# PCB_Schematic_Sheet_1.net
KiCad netlist of a schematic drawn in Altium Designer
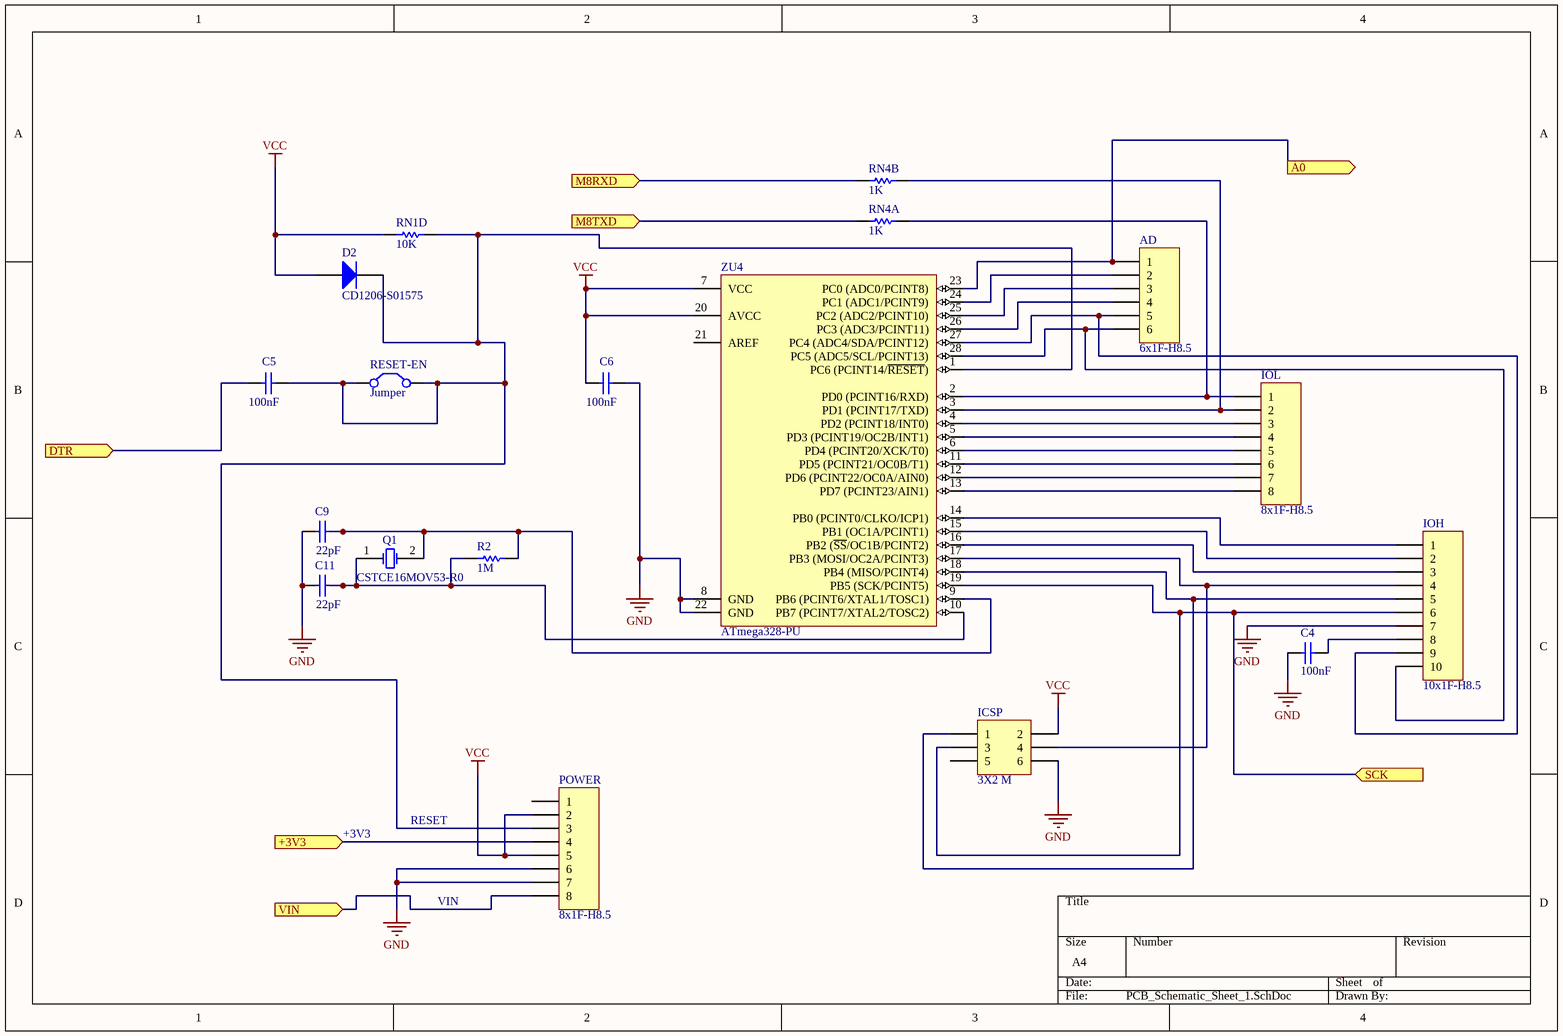
[diagram p0: PCB_Schematic_Sheet_1.SchDoc]

(export (version "E")
  (design (tool "Eeschema 10.0.6"))
  (components
    (comp (ref "AD")
      (value "6x1F-H8.5")
      (footprint "HDR1X6")
      (description "Header, 6-Pin")
      (fields (field (name "PUBLISHER") "Altium Limited"))
      (libsource (lib "Miscellaneous Connectors") (part "Header 6"))
    )
    (comp (ref "C4")
      (value "100nF")
      (footprint "CAPC0805(2012)100_M")
      (description "CAP 100nF 50V ±10% 0805 (2012 Metric) Thickness 1mm SMD")
      (fields (field (name "TOLERANCE") "Â±10%"))
      (libsource (lib "Altium Content Vault") (part "CAP"))
    )
    (comp (ref "C5")
      (value "100nF")
      (footprint "CAPC0805(2012)100_M")
      (description "CAP 100nF 50V ±10% 0805 (2012 Metric) Thickness 1mm SMD")
      (fields (field (name "TOLERANCE") "Â±10%"))
      (libsource (lib "Altium Content Vault") (part "CAP"))
    )
    (comp (ref "C6")
      (value "100nF")
      (footprint "CAPC0805(2012)100_M")
      (description "CAP 100nF 50V ±10% 0805 (2012 Metric) Thickness 1mm SMD")
      (fields (field (name "TOLERANCE") "Â±10%"))
      (libsource (lib "Altium Content Vault") (part "CAP"))
    )
    (comp (ref "C9")
      (value "22pF")
      (footprint "CAPC0805(2012)100_M")
      (description "CAP 22pF 50V ±5% 0805 (2012 Metric) Thickness 1mm SMD")
      (fields (field (name "TOLERANCE") "Â±5%"))
      (libsource (lib "Altium Content Vault") (part "CAP"))
    )
    (comp (ref "C11")
      (value "22pF")
      (footprint "CAPC0805(2012)100_M")
      (description "CAP 22pF 50V ±5% 0805 (2012 Metric) Thickness 1mm SMD")
      (fields (field (name "TOLERANCE") "Â±5%"))
      (libsource (lib "Altium Content Vault") (part "CAP"))
    )
    (comp (ref "D2")
      (value "CD1206-S01575")
      (footprint "BOUR-CD1206-S01575-2_L")
      (description "75 V Small Signal Switching Diode, 150 mA, 2.5 uA, 1026 Molded Package, RoHS, Tape and Reel")
      (fields (field (name "MANUFACTURER") "Bourns"))
      (libsource (lib "Altium Content Vault") (part "BOUR-A1K2-2"))
    )
    (comp (ref "ICSP")
      (value "3X2 M")
      (footprint "HDR2X3")
      (description "Header, 3-Pin, Dual row")
      (fields (field (name "PUBLISHER") "Altium Limited"))
      (libsource (lib "Miscellaneous Connectors") (part "Header 3X2"))
    )
    (comp (ref "IOH")
      (value "10x1F-H8.5")
      (footprint "HDR1X10")
      (description "Header, 10-Pin")
      (fields (field (name "PUBLISHER") "Altium Limited"))
      (libsource (lib "Miscellaneous Connectors") (part "Header 10"))
    )
    (comp (ref "IOL")
      (value "8x1F-H8.5")
      (footprint "HDR1X8")
      (description "Header, 8-Pin")
      (fields (field (name "PUBLISHER") "Altium Limited"))
      (libsource (lib "Miscellaneous Connectors") (part "Header 8"))
    )
    (comp (ref "POWER")
      (value "8x1F-H8.5")
      (footprint "HDR1X8")
      (description "Header, 8-Pin")
      (fields (field (name "PUBLISHER") "Altium Limited"))
      (libsource (lib "Miscellaneous Connectors") (part "Header 8"))
    )
    (comp (ref "Q1")
      (value "CSTCE16MOV53-R0")
      (footprint "R38")
      (description "Crystal Oscillator")
      (fields (field (name "PUBLISHER") "Altium Limited"))
      (libsource (lib "Miscellaneous Devices") (part "XTAL"))
    )
    (comp (ref "R2")
      (value "1M")
      (footprint "RESC0805(2012)_N")
      (description "1M 0.125W 1% 0805 (2012 Metric)  SMD")
      (fields (field (name "POWER") "0.125 W") (field (name "TOLERANCE") "1 %"))
      (libsource (lib "Altium Content Vault") (part "RES"))
    )
    (comp (ref "RESET-EN")
      (value "Jumper")
      (footprint "RAD-0.2")
      (description "Jumper Wire")
      (fields (field (name "PUBLISHER") "Altium Limited"))
      (libsource (lib "Miscellaneous Devices") (part "Jumper"))
    )
    (comp (ref "RN1D")
      (value "10K")
      (footprint "RESC0805(2012)_M")
      (description "10K 0.125W 1% 0805 (2012 Metric)  SMD")
      (fields (field (name "TOLERANCE") "1 %") (field (name "POWER") "0.125 W"))
      (libsource (lib "Altium Content Vault") (part "RES"))
    )
    (comp (ref "RN4A")
      (value "1K")
      (footprint "RESC0805(2012)_M")
      (description "1K 0.125W 1% 0805 (2012 Metric)  SMD")
      (fields (field (name "TOLERANCE") "1 %") (field (name "POWER") "0.125 W"))
      (libsource (lib "Altium Content Vault") (part "RES"))
    )
    (comp (ref "RN4B")
      (value "1K")
      (footprint "RESC0805(2012)_M")
      (description "1K 0.125W 1% 0805 (2012 Metric)  SMD")
      (fields (field (name "TOLERANCE") "1 %") (field (name "POWER") "0.125 W"))
      (libsource (lib "Altium Content Vault") (part "RES"))
    )
    (comp (ref "ZU4")
      (value "ATmega328-PU")
      (footprint "28P3")
      (libsource (lib "Altium Content Vault") (part "MC-8B-ATM48-IL28"))
    )
  )
  (nets
    (net (code "1") (name "/+3V3") (class "Default")
      (node (ref "POWER") (pin "4") (pinfunction "4_4") (pintype "passive"))
    )
    (net (code "2") (name "/A0") (class "Default")
      (node (ref "AD") (pin "1") (pinfunction "1_1") (pintype "passive"))
      (node (ref "ZU4") (pin "23") (pinfunction "PC0_(ADC0/PCINT8)_23") (pintype "bidirectional"))
    )
    (net (code "3") (name "/DTR") (class "Default")
      (node (ref "C5") (pin "1") (pinfunction "1_1") (pintype "passive"))
    )
    (net (code "4") (name "/M8RXD") (class "Default")
      (node (ref "RN4B") (pin "1") (pinfunction "1_1") (pintype "passive"))
    )
    (net (code "5") (name "/M8TXD") (class "Default")
      (node (ref "RN4A") (pin "1") (pinfunction "1_1") (pintype "passive"))
    )
    (net (code "6") (name "/SCK") (class "Default")
      (node (ref "ICSP") (pin "3") (pinfunction "3_3") (pintype "passive"))
      (node (ref "IOH") (pin "6") (pinfunction "6_6") (pintype "passive"))
      (node (ref "ZU4") (pin "19") (pinfunction "PB5_(SCK/PCINT5)_19") (pintype "bidirectional"))
    )
    (net (code "7") (name "/VIN") (class "Default")
      (node (ref "POWER") (pin "8") (pinfunction "8_8") (pintype "passive"))
    )
    (net (code "8") (name "GND") (class "Default")
      (node (ref "C11") (pin "1") (pinfunction "1_1") (pintype "passive"))
      (node (ref "C4") (pin "1") (pinfunction "1_1") (pintype "passive"))
      (node (ref "C6") (pin "2") (pinfunction "2_2") (pintype "passive"))
      (node (ref "C9") (pin "1") (pinfunction "1_1") (pintype "passive"))
      (node (ref "ICSP") (pin "6") (pinfunction "6_6") (pintype "passive"))
      (node (ref "IOH") (pin "7") (pinfunction "7_7") (pintype "passive"))
      (node (ref "POWER") (pin "6") (pinfunction "6_6") (pintype "passive"))
      (node (ref "POWER") (pin "7") (pinfunction "7_7") (pintype "passive"))
      (node (ref "ZU4") (pin "22") (pinfunction "GND_22") (pintype "power_in"))
      (node (ref "ZU4") (pin "8") (pinfunction "GND_8") (pintype "power_in"))
    )
    (net (code "9") (name "Net-(C4-Pad2)") (class "Default")
      (node (ref "C4") (pin "2") (pinfunction "2_2") (pintype "passive"))
      (node (ref "IOH") (pin "8") (pinfunction "8_8") (pintype "passive"))
    )
    (net (code "10") (name "Net-(D2-K)") (class "Default")
      (node (ref "C5") (pin "2") (pinfunction "2_2") (pintype "passive"))
      (node (ref "D2") (pin "2") (pinfunction "K_2") (pintype "passive"))
      (node (ref "POWER") (pin "3") (pinfunction "3_3") (pintype "passive"))
      (node (ref "RESET-EN") (pin "1") (pinfunction "C1_1") (pintype "passive"))
      (node (ref "RESET-EN") (pin "2") (pinfunction "C2_2") (pintype "passive"))
      (node (ref "RN1D") (pin "2") (pinfunction "2_2") (pintype "passive"))
      (node (ref "ZU4") (pin "1") (pinfunction "PC6_(PCINT14/~{RESET})_1") (pintype "bidirectional"))
    )
    (net (code "11") (name "Net-(Q1-OSC1)") (class "Default")
      (node (ref "C11") (pin "2") (pinfunction "2_2") (pintype "passive"))
      (node (ref "Q1") (pin "1") (pinfunction "OSC1_1") (pintype "passive"))
      (node (ref "R2") (pin "1") (pinfunction "1_1") (pintype "passive"))
      (node (ref "ZU4") (pin "10") (pinfunction "PB7_(PCINT7/XTAL2/TOSC2)_10") (pintype "bidirectional"))
    )
    (net (code "12") (name "Net-(Q1-OSC2)") (class "Default")
      (node (ref "C9") (pin "2") (pinfunction "2_2") (pintype "passive"))
      (node (ref "Q1") (pin "2") (pinfunction "OSC2_2") (pintype "passive"))
      (node (ref "R2") (pin "2") (pinfunction "2_2") (pintype "passive"))
      (node (ref "ZU4") (pin "9") (pinfunction "PB6_(PCINT6/XTAL1/TOSC1)_9") (pintype "bidirectional"))
    )
    (net (code "13") (name "Net-(ZU4-PB0_(PCINT0{slash}CLKO{slash}ICP1))") (class "Default")
      (node (ref "IOH") (pin "1") (pinfunction "1_1") (pintype "passive"))
      (node (ref "ZU4") (pin "14") (pinfunction "PB0_(PCINT0/CLKO/ICP1)_14") (pintype "bidirectional"))
    )
    (net (code "14") (name "Net-(ZU4-PB1_(OC1A{slash}PCINT1))") (class "Default")
      (node (ref "IOH") (pin "2") (pinfunction "2_2") (pintype "passive"))
      (node (ref "ZU4") (pin "15") (pinfunction "PB1_(OC1A/PCINT1)_15") (pintype "bidirectional"))
    )
    (net (code "15") (name "Net-(ZU4-PB2_(~{SS}{slash}OC1B{slash}PCINT2))") (class "Default")
      (node (ref "IOH") (pin "3") (pinfunction "3_3") (pintype "passive"))
      (node (ref "ZU4") (pin "16") (pinfunction "PB2_(~{SS}/OC1B/PCINT2)_16") (pintype "bidirectional"))
    )
    (net (code "16") (name "Net-(ZU4-PB3_(MOSI{slash}OC2A{slash}PCINT3))") (class "Default")
      (node (ref "ICSP") (pin "4") (pinfunction "4_4") (pintype "passive"))
      (node (ref "IOH") (pin "4") (pinfunction "4_4") (pintype "passive"))
      (node (ref "ZU4") (pin "17") (pinfunction "PB3_(MOSI/OC2A/PCINT3)_17") (pintype "bidirectional"))
    )
    (net (code "17") (name "Net-(ZU4-PB4_(MISO{slash}PCINT4))") (class "Default")
      (node (ref "ICSP") (pin "1") (pinfunction "1_1") (pintype "passive"))
      (node (ref "IOH") (pin "5") (pinfunction "5_5") (pintype "passive"))
      (node (ref "ZU4") (pin "18") (pinfunction "PB4_(MISO/PCINT4)_18") (pintype "bidirectional"))
    )
    (net (code "18") (name "Net-(ZU4-PC1_(ADC1{slash}PCINT9))") (class "Default")
      (node (ref "AD") (pin "2") (pinfunction "2_2") (pintype "passive"))
      (node (ref "ZU4") (pin "24") (pinfunction "PC1_(ADC1/PCINT9)_24") (pintype "bidirectional"))
    )
    (net (code "19") (name "Net-(ZU4-PC2_(ADC2{slash}PCINT10))") (class "Default")
      (node (ref "AD") (pin "3") (pinfunction "3_3") (pintype "passive"))
      (node (ref "ZU4") (pin "25") (pinfunction "PC2_(ADC2/PCINT10)_25") (pintype "bidirectional"))
    )
    (net (code "20") (name "Net-(ZU4-PC3_(ADC3{slash}PCINT11))") (class "Default")
      (node (ref "AD") (pin "4") (pinfunction "4_4") (pintype "passive"))
      (node (ref "ZU4") (pin "26") (pinfunction "PC3_(ADC3/PCINT11)_26") (pintype "bidirectional"))
    )
    (net (code "21") (name "Net-(ZU4-PC4_(ADC4{slash}SDA{slash}PCINT12))") (class "Default")
      (node (ref "AD") (pin "5") (pinfunction "5_5") (pintype "passive"))
      (node (ref "IOH") (pin "9") (pinfunction "9_9") (pintype "passive"))
      (node (ref "ZU4") (pin "27") (pinfunction "PC4_(ADC4/SDA/PCINT12)_27") (pintype "bidirectional"))
    )
    (net (code "22") (name "Net-(ZU4-PC5_(ADC5{slash}SCL{slash}PCINT13))") (class "Default")
      (node (ref "AD") (pin "6") (pinfunction "6_6") (pintype "passive"))
      (node (ref "IOH") (pin "10") (pinfunction "10_10") (pintype "passive"))
      (node (ref "ZU4") (pin "28") (pinfunction "PC5_(ADC5/SCL/PCINT13)_28") (pintype "bidirectional"))
    )
    (net (code "23") (name "Net-(ZU4-PD0_(PCINT16{slash}RXD))") (class "Default")
      (node (ref "IOL") (pin "1") (pinfunction "1_1") (pintype "passive"))
      (node (ref "RN4A") (pin "2") (pinfunction "2_2") (pintype "passive"))
      (node (ref "ZU4") (pin "2") (pinfunction "PD0_(PCINT16/RXD)_2") (pintype "bidirectional"))
    )
    (net (code "24") (name "Net-(ZU4-PD1_(PCINT17{slash}TXD))") (class "Default")
      (node (ref "IOL") (pin "2") (pinfunction "2_2") (pintype "passive"))
      (node (ref "RN4B") (pin "2") (pinfunction "2_2") (pintype "passive"))
      (node (ref "ZU4") (pin "3") (pinfunction "PD1_(PCINT17/TXD)_3") (pintype "bidirectional"))
    )
    (net (code "25") (name "Net-(ZU4-PD2_(PCINT18{slash}INT0))") (class "Default")
      (node (ref "IOL") (pin "3") (pinfunction "3_3") (pintype "passive"))
      (node (ref "ZU4") (pin "4") (pinfunction "PD2_(PCINT18/INT0)_4") (pintype "bidirectional"))
    )
    (net (code "26") (name "Net-(ZU4-PD3_(PCINT19{slash}OC2B{slash}INT1))") (class "Default")
      (node (ref "IOL") (pin "4") (pinfunction "4_4") (pintype "passive"))
      (node (ref "ZU4") (pin "5") (pinfunction "PD3_(PCINT19/OC2B/INT1)_5") (pintype "bidirectional"))
    )
    (net (code "27") (name "Net-(ZU4-PD4_(PCINT20{slash}XCK{slash}T0))") (class "Default")
      (node (ref "IOL") (pin "5") (pinfunction "5_5") (pintype "passive"))
      (node (ref "ZU4") (pin "6") (pinfunction "PD4_(PCINT20/XCK/T0)_6") (pintype "bidirectional"))
    )
    (net (code "28") (name "Net-(ZU4-PD5_(PCINT21{slash}OC0B{slash}T1))") (class "Default")
      (node (ref "IOL") (pin "6") (pinfunction "6_6") (pintype "passive"))
      (node (ref "ZU4") (pin "11") (pinfunction "PD5_(PCINT21/OC0B/T1)_11") (pintype "bidirectional"))
    )
    (net (code "29") (name "Net-(ZU4-PD6_(PCINT22{slash}OC0A{slash}AIN0))") (class "Default")
      (node (ref "IOL") (pin "7") (pinfunction "7_7") (pintype "passive"))
      (node (ref "ZU4") (pin "12") (pinfunction "PD6_(PCINT22/OC0A/AIN0)_12") (pintype "bidirectional"))
    )
    (net (code "30") (name "Net-(ZU4-PD7_(PCINT23{slash}AIN1))") (class "Default")
      (node (ref "IOL") (pin "8") (pinfunction "8_8") (pintype "passive"))
      (node (ref "ZU4") (pin "13") (pinfunction "PD7_(PCINT23/AIN1)_13") (pintype "bidirectional"))
    )
    (net (code "31") (name "VCC") (class "Default")
      (node (ref "C6") (pin "1") (pinfunction "1_1") (pintype "passive"))
      (node (ref "D2") (pin "1") (pinfunction "A_1") (pintype "passive"))
      (node (ref "ICSP") (pin "2") (pinfunction "2_2") (pintype "passive"))
      (node (ref "POWER") (pin "2") (pinfunction "2_2") (pintype "passive"))
      (node (ref "POWER") (pin "5") (pinfunction "5_5") (pintype "passive"))
      (node (ref "RN1D") (pin "1") (pinfunction "1_1") (pintype "passive"))
      (node (ref "ZU4") (pin "20") (pinfunction "AVCC_20") (pintype "power_in"))
      (node (ref "ZU4") (pin "7") (pinfunction "VCC_7") (pintype "power_in"))
    )
    (net (code "32") (name "unconnected-(ICSP-Pad5)") (class "Default")
      (node (ref "ICSP") (pin "5") (pinfunction "5_5") (pintype "passive"))
    )
    (net (code "33") (name "unconnected-(POWER-Pad1)") (class "Default")
      (node (ref "POWER") (pin "1") (pinfunction "1_1") (pintype "passive"))
    )
    (net (code "34") (name "unconnected-(ZU4-AREF-Pad21)") (class "Default")
      (node (ref "ZU4") (pin "21") (pinfunction "AREF_21") (pintype "power_in"))
    )
  )
)
